# POWER.net
KiCad netlist of a schematic drawn in Altium Designer
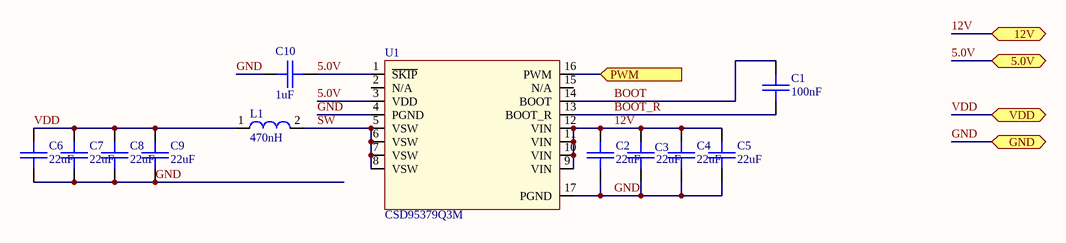
[diagram p0: POWER.SchDoc]

(export (version "E")
  (design (tool "Eeschema 10.0.6"))
  (components
    (comp (ref "C1") (value "100nF") (footprint "SMD_0603_CAPC1608X95N") (libsource (lib "DLV") (part "C")))
    (comp (ref "C2") (value "22uF") (footprint "SMD_0805_CAPC2012X95N") (libsource (lib "DLV") (part "C")))
    (comp (ref "C3") (value "22uF") (footprint "SMD_0805_CAPC2012X95N") (libsource (lib "DLV") (part "C")))
    (comp (ref "C4") (value "22uF") (footprint "SMD_0805_CAPC2012X95N") (libsource (lib "DLV") (part "C")))
    (comp (ref "C5") (value "22uF") (footprint "SMD_0805_CAPC2012X95N") (libsource (lib "DLV") (part "C")))
    (comp (ref "C6") (value "22uF") (footprint "SMD_0805_CAPC2012X95N") (libsource (lib "DLV") (part "C")))
    (comp (ref "C7") (value "22uF") (footprint "SMD_0805_CAPC2012X95N") (libsource (lib "DLV") (part "C")))
    (comp (ref "C8") (value "22uF") (footprint "SMD_0805_CAPC2012X95N") (libsource (lib "DLV") (part "C")))
    (comp (ref "C9") (value "22uF") (footprint "SMD_0805_CAPC2012X95N") (libsource (lib "DLV") (part "C")))
    (comp (ref "C10") (value "1uF") (footprint "SMD_0603_CAPC1608X95N") (libsource (lib "DLV") (part "C")))
    (comp (ref "L1") (value "470nH") (footprint "SMD_INDM720X665X300") (libsource (lib "DLV") (part "L")))
    (comp (ref "U1")
      (value "CSD95379Q3M")
      (footprint "SMD_SON50P340X340X80-21N - VSON10")
      (description "Texas Instrumendts Buck Boost DC-DC")
      (libsource (lib "DLV") (part "IC_CSD95379Q3M"))
    )
  )
  (nets
    (net (code "1") (name "/5.0V") (class "Default")
      (node (ref "C10") (pin "1") (pinfunction "1_1") (pintype "passive"))
      (node (ref "U1") (pin "1") (pinfunction "~{SKIP}_1") (pintype "passive"))
      (node (ref "U1") (pin "3") (pinfunction "VDD_3") (pintype "passive"))
    )
    (net (code "2") (name "/12V") (class "Default")
      (node (ref "C2") (pin "1") (pinfunction "1_1") (pintype "passive"))
      (node (ref "C3") (pin "1") (pinfunction "1_1") (pintype "passive"))
      (node (ref "C4") (pin "1") (pinfunction "1_1") (pintype "passive"))
      (node (ref "C5") (pin "1") (pinfunction "1_1") (pintype "passive"))
      (node (ref "U1") (pin "10") (pinfunction "VIN_10") (pintype "passive"))
      (node (ref "U1") (pin "11") (pinfunction "VIN_11") (pintype "passive"))
      (node (ref "U1") (pin "12") (pinfunction "VIN_12") (pintype "passive"))
      (node (ref "U1") (pin "9") (pinfunction "VIN_9") (pintype "passive"))
    )
    (net (code "3") (name "/BOOT") (class "Default")
      (node (ref "C1") (pin "1") (pinfunction "1_1") (pintype "passive"))
      (node (ref "U1") (pin "14") (pinfunction "BOOT_14") (pintype "passive"))
    )
    (net (code "4") (name "/BOOT_R") (class "Default")
      (node (ref "C1") (pin "2") (pinfunction "2_2") (pintype "passive"))
      (node (ref "U1") (pin "13") (pinfunction "BOOT_R_13") (pintype "passive"))
    )
    (net (code "5") (name "/GND") (class "Default")
      (node (ref "C10") (pin "2") (pinfunction "2_2") (pintype "passive"))
      (node (ref "C2") (pin "2") (pinfunction "2_2") (pintype "passive"))
      (node (ref "C3") (pin "2") (pinfunction "2_2") (pintype "passive"))
      (node (ref "C4") (pin "2") (pinfunction "2_2") (pintype "passive"))
      (node (ref "C5") (pin "2") (pinfunction "2_2") (pintype "passive"))
      (node (ref "C6") (pin "2") (pinfunction "2_2") (pintype "passive"))
      (node (ref "C7") (pin "2") (pinfunction "2_2") (pintype "passive"))
      (node (ref "C8") (pin "2") (pinfunction "2_2") (pintype "passive"))
      (node (ref "C9") (pin "2") (pinfunction "2_2") (pintype "passive"))
      (node (ref "U1") (pin "17") (pinfunction "PGND_17") (pintype "passive"))
      (node (ref "U1") (pin "4") (pinfunction "PGND_4") (pintype "passive"))
    )
    (net (code "6") (name "/PWM") (class "Default")
      (node (ref "U1") (pin "16") (pinfunction "PWM_16") (pintype "passive"))
    )
    (net (code "7") (name "/SW") (class "Default")
      (node (ref "L1") (pin "2") (pinfunction "2_2") (pintype "passive"))
      (node (ref "U1") (pin "5") (pinfunction "VSW_5") (pintype "passive"))
      (node (ref "U1") (pin "6") (pinfunction "VSW_6") (pintype "passive"))
      (node (ref "U1") (pin "7") (pinfunction "VSW_7") (pintype "passive"))
      (node (ref "U1") (pin "8") (pinfunction "VSW_8") (pintype "passive"))
    )
    (net (code "8") (name "/VDD") (class "Default")
      (node (ref "C6") (pin "1") (pinfunction "1_1") (pintype "passive"))
      (node (ref "C7") (pin "1") (pinfunction "1_1") (pintype "passive"))
      (node (ref "C8") (pin "1") (pinfunction "1_1") (pintype "passive"))
      (node (ref "C9") (pin "1") (pinfunction "1_1") (pintype "passive"))
      (node (ref "L1") (pin "1") (pinfunction "1_1") (pintype "passive"))
    )
    (net (code "9") (name "unconnected-(U1-N{slash}A-Pad2)") (class "Default")
      (node (ref "U1") (pin "2") (pinfunction "N/A_2") (pintype "passive"))
    )
    (net (code "10") (name "unconnected-(U1-N{slash}A-Pad15)") (class "Default")
      (node (ref "U1") (pin "15") (pinfunction "N/A_15") (pintype "passive"))
    )
  )
)
